# ICM-42688-P_Module.net
KiCad netlist of a schematic drawn in EAGLE
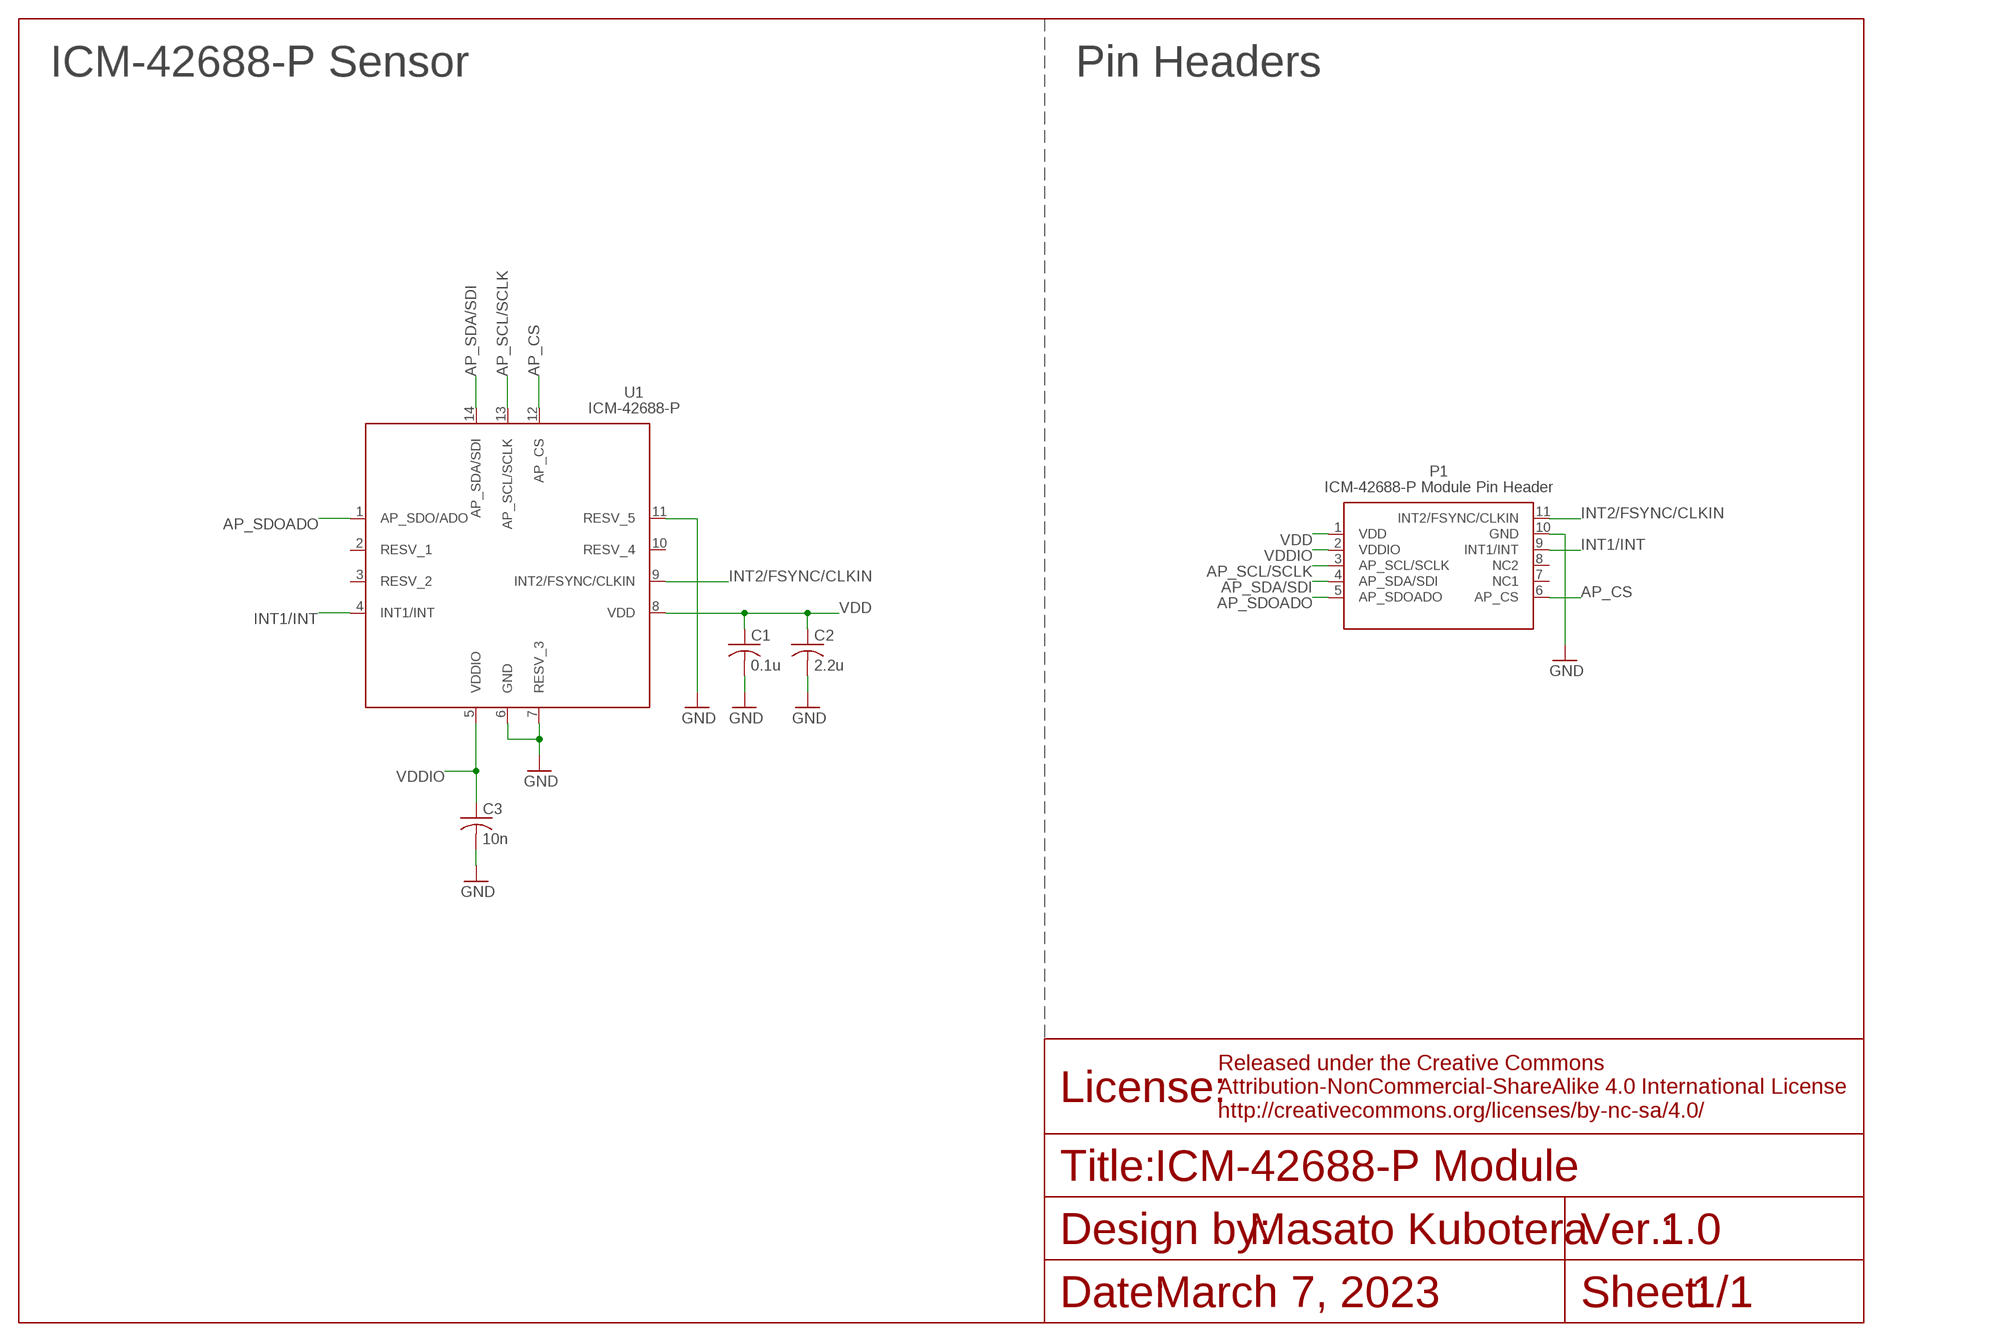
[diagram p0: schematic, sheet 1]

(export (version "E")
  (design (tool "Eeschema 10.0.6"))
  (components
    (comp (ref "C1")
      (value "0.1u")
      (footprint "eagle-import:C0402")
      (libsource (lib "eagle-import") (part "C-USC0402"))
    )
    (comp (ref "C2")
      (value "2.2u")
      (footprint "eagle-import:C0402")
      (libsource (lib "eagle-import") (part "C-USC0402"))
    )
    (comp (ref "C3")
      (value "10n")
      (footprint "eagle-import:C0402")
      (libsource (lib "eagle-import") (part "C-USC0402"))
    )
    (comp (ref "P1")
      (value "ICM-42688-P-MODULE-PINHEADER")
      (footprint "eagle-import:FOR-MODULE-MAKING")
      (libsource (lib "eagle-import") (part "ICM-42688-P-MODULE-PINHEADER"))
    )
    (comp (ref "U1")
      (value "ICM-42688-P")
      (footprint "eagle-import:ICM-42688-P")
      (libsource (lib "eagle-import") (part "ICM-42688-P"))
    )
  )
  (nets
    (net (code "1") (name "/AP_CS") (class "Default")
      (node (ref "P1") (pin "6") (pinfunction "AP_CS_6") (pintype "bidirectional"))
      (node (ref "U1") (pin "12") (pinfunction "AP_CS_12") (pintype "bidirectional"))
    )
    (net (code "2") (name "/AP_SCL{slash}SCLK") (class "Default")
      (node (ref "P1") (pin "3") (pinfunction "AP_SCL/SCLK_3") (pintype "bidirectional"))
      (node (ref "U1") (pin "13") (pinfunction "AP_SCL/SCLK_13") (pintype "bidirectional"))
    )
    (net (code "3") (name "/AP_SDA{slash}SDI") (class "Default")
      (node (ref "P1") (pin "4") (pinfunction "AP_SDA/SDI_4") (pintype "bidirectional"))
      (node (ref "U1") (pin "14") (pinfunction "AP_SDA/SDI_14") (pintype "bidirectional"))
    )
    (net (code "4") (name "/AP_SDOADO") (class "Default")
      (node (ref "P1") (pin "5") (pinfunction "AP_SDOADO_5") (pintype "bidirectional"))
      (node (ref "U1") (pin "1") (pinfunction "AP_SDO/ADO_1") (pintype "bidirectional"))
    )
    (net (code "5") (name "/INT1{slash}INT") (class "Default")
      (node (ref "P1") (pin "9") (pinfunction "INT1/INT_9") (pintype "bidirectional"))
      (node (ref "U1") (pin "4") (pinfunction "INT1/INT_4") (pintype "bidirectional"))
    )
    (net (code "6") (name "/INT2{slash}FSYNC{slash}CLKIN") (class "Default")
      (node (ref "P1") (pin "11") (pinfunction "INT2/FSYNC/CLKIN_11") (pintype "bidirectional"))
      (node (ref "U1") (pin "9") (pinfunction "INT2/FSYNC/CLKIN_9") (pintype "bidirectional"))
    )
    (net (code "7") (name "/VDD") (class "Default")
      (node (ref "C1") (pin "1") (pinfunction "1_1") (pintype "passive"))
      (node (ref "C2") (pin "1") (pinfunction "1_1") (pintype "passive"))
      (node (ref "P1") (pin "1") (pinfunction "VDD_1") (pintype "bidirectional"))
      (node (ref "U1") (pin "8") (pinfunction "VDD_8") (pintype "power_in"))
    )
    (net (code "8") (name "/VDDIO") (class "Default")
      (node (ref "C3") (pin "1") (pinfunction "1_1") (pintype "passive"))
      (node (ref "P1") (pin "2") (pinfunction "VDDIO_2") (pintype "bidirectional"))
      (node (ref "U1") (pin "5") (pinfunction "VDDIO_5") (pintype "power_in"))
    )
    (net (code "9") (name "GND") (class "Default")
      (node (ref "C1") (pin "2") (pinfunction "2_2") (pintype "passive"))
      (node (ref "C2") (pin "2") (pinfunction "2_2") (pintype "passive"))
      (node (ref "C3") (pin "2") (pinfunction "2_2") (pintype "passive"))
      (node (ref "P1") (pin "10") (pinfunction "GND_10") (pintype "bidirectional"))
      (node (ref "U1") (pin "11") (pinfunction "RESV_5_11") (pintype "bidirectional"))
      (node (ref "U1") (pin "6") (pinfunction "GND_6") (pintype "bidirectional"))
      (node (ref "U1") (pin "7") (pinfunction "RESV_3_7") (pintype "bidirectional"))
    )
    (net (code "10") (name "unconnected-(P1-NC1-Pad7)") (class "Default")
      (node (ref "P1") (pin "7") (pinfunction "NC1_7") (pintype "no_connect"))
    )
    (net (code "11") (name "unconnected-(P1-NC2-Pad8)") (class "Default")
      (node (ref "P1") (pin "8") (pinfunction "NC2_8") (pintype "no_connect"))
    )
    (net (code "12") (name "unconnected-(U1-RESV_1-Pad2)") (class "Default")
      (node (ref "U1") (pin "2") (pinfunction "RESV_1_2") (pintype "bidirectional"))
    )
    (net (code "13") (name "unconnected-(U1-RESV_2-Pad3)") (class "Default")
      (node (ref "U1") (pin "3") (pinfunction "RESV_2_3") (pintype "bidirectional"))
    )
    (net (code "14") (name "unconnected-(U1-RESV_4-Pad10)") (class "Default")
      (node (ref "U1") (pin "10") (pinfunction "RESV_4_10") (pintype "bidirectional"))
    )
  )
)
